# Unijunction_Transistor.net
KiCad netlist of a schematic drawn in Altium Designer
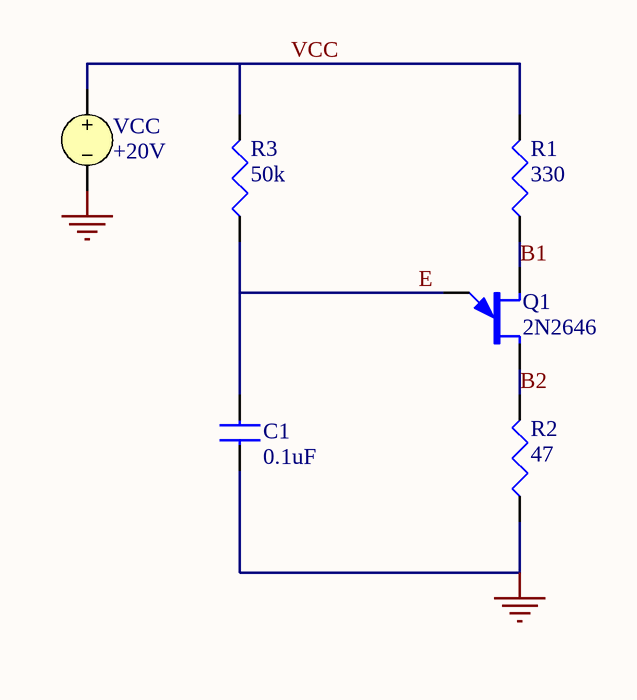
[diagram p0: Unijunction Transistor.schdoc]

(export (version "E")
  (design (tool "Eeschema 10.0.6"))
  (components
    (comp (ref "C1") (value "0.1uF") (description "Capacitor") (libsource (lib "*") (part "CAP")))
    (comp (ref "Q1")
      (value "2N2646")
      (description "Unijunction Transistor")
      (libsource (lib "*") (part "2N2646"))
    )
    (comp (ref "R1") (value "330") (description "Resistor") (libsource (lib "*") (part "RES")))
    (comp (ref "R2") (value "47") (description "Resistor") (libsource (lib "*") (part "RES")))
    (comp (ref "R3") (value "50k") (description "Resistor") (libsource (lib "*") (part "RES")))
    (comp (ref "VCC") (value "+20V") (description "Voltage Source") (libsource (lib "*") (part "VSRC")))
  )
  (nets
    (net (code "1") (name "/B1") (class "Default")
      (node (ref "Q1") (pin "1") (pinfunction "B2_1") (pintype "passive"))
      (node (ref "R1") (pin "2") (pinfunction "BOT_2") (pintype "passive"))
    )
    (net (code "2") (name "/B2") (class "Default")
      (node (ref "Q1") (pin "3") (pinfunction "B1_3") (pintype "passive"))
      (node (ref "R2") (pin "1") (pinfunction "TOP_1") (pintype "passive"))
    )
    (net (code "3") (name "/E") (class "Default")
      (node (ref "C1") (pin "1") (pinfunction "1_1") (pintype "passive"))
      (node (ref "Q1") (pin "2") (pinfunction "E_2") (pintype "passive"))
      (node (ref "R3") (pin "2") (pinfunction "BOT_2") (pintype "passive"))
    )
    (net (code "4") (name "/VCC") (class "Default")
      (node (ref "R1") (pin "1") (pinfunction "TOP_1") (pintype "passive"))
      (node (ref "R3") (pin "1") (pinfunction "TOP_1") (pintype "passive"))
      (node (ref "VCC") (pin "1") (pinfunction "1_1") (pintype "passive"))
    )
    (net (code "5") (name "GND") (class "Default")
      (node (ref "C1") (pin "2") (pinfunction "2_2") (pintype "passive"))
      (node (ref "R2") (pin "2") (pinfunction "BOT_2") (pintype "passive"))
      (node (ref "VCC") (pin "2") (pinfunction "2_2") (pintype "passive"))
    )
  )
)
